# FUZZY_LOGIC_ARDUINO.net
KiCad netlist of a schematic drawn in Altium Designer
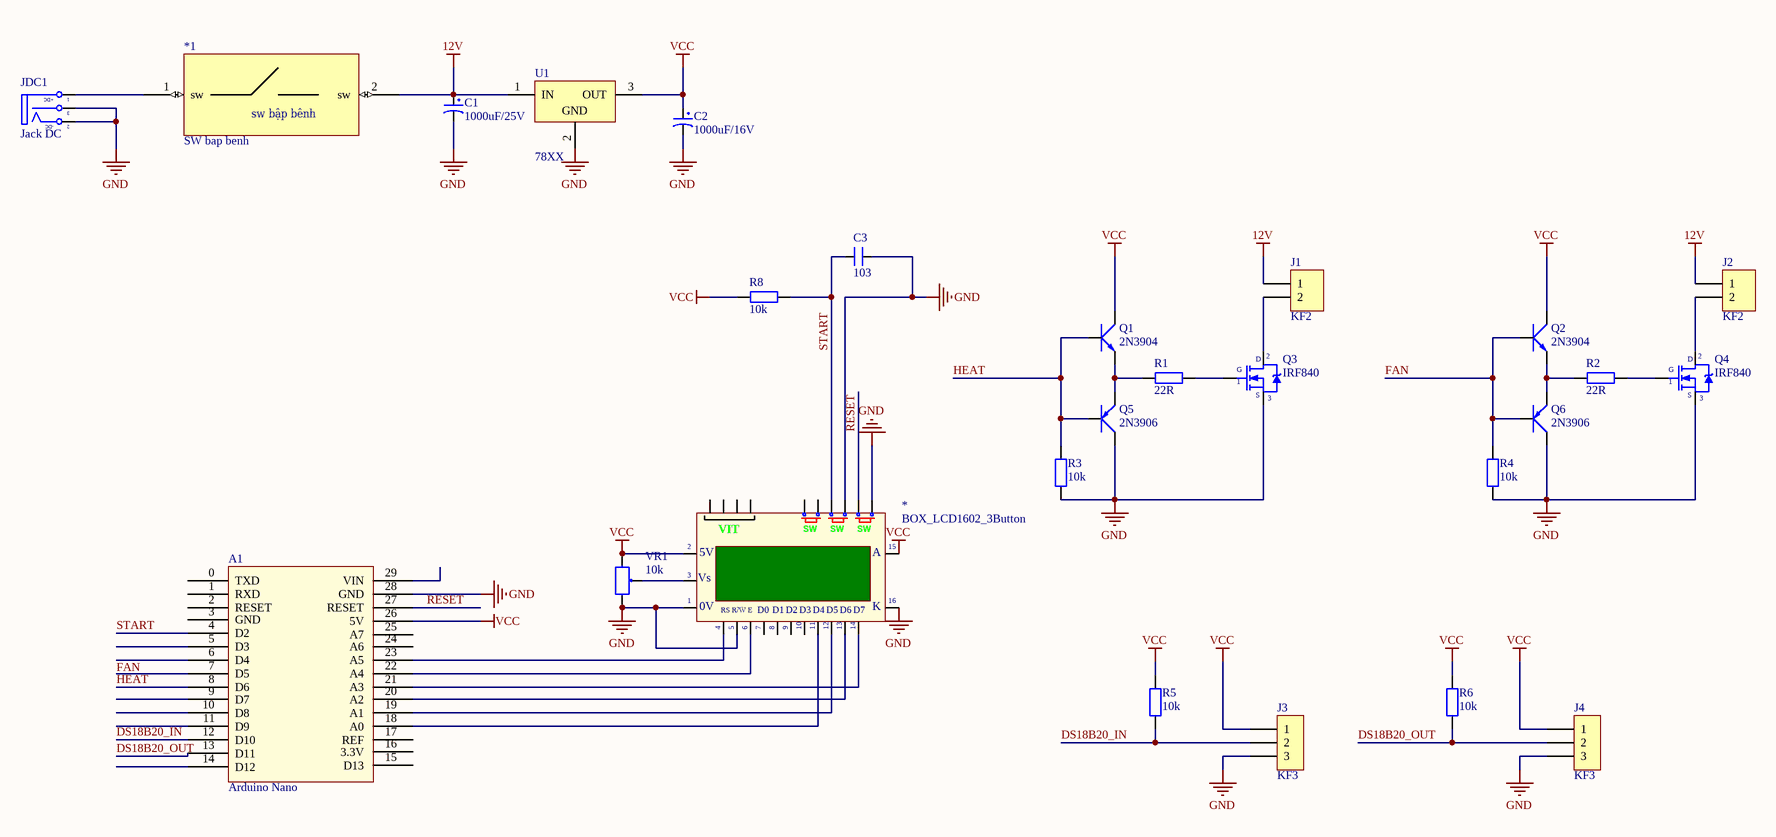
[diagram p0: FUZZY_LOGIC_ARDUINO.SchDoc]

(export (version "E")
  (design (tool "Eeschema 10.0.6"))
  (components
    (comp (ref "*")
      (value "BOX_LCD1602_3Button")
      (footprint "BOX_LCD1602_3Button")
      (libsource (lib "OBIT_TESLA") (part "BOX_LCD1602_3Button"))
    )
    (comp (ref "*1")
      (value "SW bap benh")
      (footprint "SW bapbenh")
      (libsource (lib "Sw bapbenh") (part "SW bap benh"))
    )
    (comp (ref "A1")
      (value "Arduino Nano")
      (footprint "Arduino Nano")
      (libsource (lib "OBIT_TESLA") (part "Arduino Nano"))
    )
    (comp (ref "C1")
      (value "1000uF/25V")
      (footprint "CP1.5/3.4")
      (description "Cap 1000uF/16V - 220uF/50V")
      (libsource (lib "OBIT_TESLA") (part "CP4"))
    )
    (comp (ref "C2")
      (value "1000uF/16V")
      (footprint "CP1.5/3.4")
      (description "Cap 1000uF/16V - 220uF/50V")
      (libsource (lib "OBIT_TESLA") (part "CP4"))
    )
    (comp (ref "C3")
      (value "103")
      (footprint "SM-0805")
      (description "Cap SMD")
      (libsource (lib "OBIT_TESLA") (part "CM"))
    )
    (comp (ref "J1")
      (value "KF2")
      (footprint "KF2-3.5")
      (fields
        (field (name "MANUFACTURER") "Würth Elektronik eiSos GmbH")
        (field (name "PARTNO") "691103110002")
        (field (name "CREATED BY") "Karrer Zheng")
      )
      (libsource (lib "OBIT_TESLA") (part "KF2"))
    )
    (comp (ref "J2")
      (value "KF2")
      (footprint "KF2-3.5")
      (fields
        (field (name "MANUFACTURER") "Würth Elektronik eiSos GmbH")
        (field (name "PARTNO") "691103110002")
        (field (name "CREATED BY") "Karrer Zheng")
      )
      (libsource (lib "OBIT_TESLA") (part "KF2"))
    )
    (comp (ref "J3")
      (value "KF3")
      (footprint "KF3-5.08")
      (fields
        (field (name "MANUFACTURER") "Würth Elektronik eiSos GmbH")
        (field (name "PARTNO") "691103110003")
        (field (name "CREATED BY") "Karrer Zheng")
      )
      (libsource (lib "OBIT_TESLA") (part "KF3"))
    )
    (comp (ref "J4")
      (value "KF3")
      (footprint "KF3-5.08")
      (fields
        (field (name "MANUFACTURER") "Würth Elektronik eiSos GmbH")
        (field (name "PARTNO") "691103110003")
        (field (name "CREATED BY") "Karrer Zheng")
      )
      (libsource (lib "OBIT_TESLA") (part "KF3"))
    )
    (comp (ref "JDC1") (value "Jack DC") (footprint "DC0") (libsource (lib "OBIT_TESLA") (part "JACK_DC")))
    (comp (ref "Q1")
      (value "2N3904")
      (footprint "TO92-123")
      (description "NPN 600mW, ECB")
      (libsource (lib "Tesla_Thinh") (part "2N904"))
    )
    (comp (ref "Q2")
      (value "2N3904")
      (footprint "TO92-123")
      (description "NPN 600mW, ECB")
      (libsource (lib "Tesla_Thinh") (part "2N904"))
    )
    (comp (ref "Q3")
      (value "IRF840")
      (footprint "TO252-123")
      (description "MOSFET N - CHANNEL 500V - 0.75 - 8A - TO-220")
      (libsource (lib "Tesla_Thinh") (part "IRF840"))
    )
    (comp (ref "Q4")
      (value "IRF840")
      (footprint "TO252-123")
      (description "MOSFET N - CHANNEL 500V - 0.75 - 8A - TO-220")
      (libsource (lib "Tesla_Thinh") (part "IRF840"))
    )
    (comp (ref "Q5")
      (value "2N3906")
      (footprint "TO92-123")
      (description "PNP 600mW, ECB")
      (libsource (lib "Tesla_Thinh") (part "2N3906"))
    )
    (comp (ref "Q6")
      (value "2N3906")
      (footprint "TO92-123")
      (description "PNP 600mW, ECB")
      (libsource (lib "Tesla_Thinh") (part "2N3906"))
    )
    (comp (ref "R1")
      (value "22R")
      (footprint "R1/4W")
      (description "Resistor 1/4W")
      (libsource (lib "Tesla_Thinh") (part "R1/4W"))
    )
    (comp (ref "R2")
      (value "22R")
      (footprint "R1/4W")
      (description "Resistor 1/4W")
      (libsource (lib "Tesla_Thinh") (part "R1/4W"))
    )
    (comp (ref "R3")
      (value "10k")
      (footprint "SM-RES-0805")
      (description "Resistor 1/4W")
      (libsource (lib "Tesla_Thinh") (part "R1/4W"))
    )
    (comp (ref "R4")
      (value "10k")
      (footprint "SM-RES-0805")
      (description "Resistor 1/4W")
      (libsource (lib "Tesla_Thinh") (part "R1/4W"))
    )
    (comp (ref "R5")
      (value "10k")
      (footprint "SM-RES-0805")
      (description "Resistor 1/4W")
      (libsource (lib "Tesla_Thinh") (part "R1/4W"))
    )
    (comp (ref "R6")
      (value "10k")
      (footprint "SM-RES-0805")
      (description "Resistor 1/4W")
      (libsource (lib "Tesla_Thinh") (part "R1/4W"))
    )
    (comp (ref "R8")
      (value "10k")
      (footprint "SM-RES-0805")
      (description "Resistor 1/4W")
      (libsource (lib "Tesla_Thinh") (part "R1/4W"))
    )
    (comp (ref "U1") (value "78XX") (footprint "TO252-123") (libsource (lib "OBIT_TESLA") (part "LM78XX")))
    (comp (ref "VR1") (value "10k") (footprint "VR-S2") (libsource (lib "OBIT_TESLA") (part "Resistor Var")))
  )
  (nets
    (net (code "1") (name "/DS18B20_IN") (class "Default")
      (node (ref "A1") (pin "12") (pinfunction "D10_12") (pintype "passive"))
      (node (ref "J3") (pin "2") (pinfunction "2_2") (pintype "passive"))
      (node (ref "R5") (pin "1") (pinfunction "1_1") (pintype "passive"))
    )
    (net (code "2") (name "/DS18B20_OUT") (class "Default")
      (node (ref "A1") (pin "13") (pinfunction "D11_13") (pintype "passive"))
      (node (ref "J4") (pin "2") (pinfunction "2_2") (pintype "passive"))
      (node (ref "R6") (pin "1") (pinfunction "1_1") (pintype "passive"))
    )
    (net (code "3") (name "/FAN") (class "Default")
      (node (ref "Q2") (pin "2") (pinfunction "B_2") (pintype "passive"))
      (node (ref "Q6") (pin "2") (pinfunction "B_2") (pintype "passive"))
      (node (ref "R4") (pin "2") (pinfunction "2_2") (pintype "passive"))
    )
    (net (code "4") (name "/HEAT") (class "Default")
      (node (ref "A1") (pin "8") (pinfunction "D6_8") (pintype "passive"))
      (node (ref "Q1") (pin "2") (pinfunction "B_2") (pintype "passive"))
      (node (ref "Q5") (pin "2") (pinfunction "B_2") (pintype "passive"))
      (node (ref "R3") (pin "2") (pinfunction "2_2") (pintype "passive"))
    )
    (net (code "5") (name "/RESET") (class "Default")
      (node (ref "*") (pin "21") (pinfunction "21_21") (pintype "passive"))
      (node (ref "A1") (pin "27") (pinfunction "RESET_27") (pintype "passive"))
    )
    (net (code "6") (name "/START") (class "Default")
      (node (ref "*") (pin "19") (pinfunction "19_19") (pintype "passive"))
      (node (ref "A1") (pin "4") (pinfunction "D2_4") (pintype "passive"))
      (node (ref "C3") (pin "1") (pinfunction "1_1") (pintype "passive"))
      (node (ref "R8") (pin "1") (pinfunction "1_1") (pintype "passive"))
    )
    (net (code "7") (name "12V") (class "Default")
      (node (ref "*1") (pin "2") (pinfunction "sw_2") (pintype "bidirectional"))
      (node (ref "C1") (pin "1") (pinfunction "1_1") (pintype "passive"))
      (node (ref "J1") (pin "1") (pinfunction "1_1") (pintype "passive"))
      (node (ref "J2") (pin "1") (pinfunction "1_1") (pintype "passive"))
      (node (ref "U1") (pin "1") (pinfunction "IN_1") (pintype "power_in"))
    )
    (net (code "8") (name "GND") (class "Default")
      (node (ref "*") (pin "1") (pinfunction "GND_1") (pintype "passive"))
      (node (ref "*") (pin "16") (pinfunction "K_16") (pintype "passive"))
      (node (ref "*") (pin "20") (pinfunction "20_20") (pintype "passive"))
      (node (ref "*") (pin "22") (pinfunction "22_22") (pintype "passive"))
      (node (ref "*") (pin "5") (pinfunction "R/~{W}_5") (pintype "passive"))
      (node (ref "A1") (pin "28") (pinfunction "GND_28") (pintype "passive"))
      (node (ref "C1") (pin "2") (pinfunction "2_2") (pintype "passive"))
      (node (ref "C2") (pin "2") (pinfunction "2_2") (pintype "passive"))
      (node (ref "C3") (pin "2") (pinfunction "2_2") (pintype "passive"))
      (node (ref "J3") (pin "3") (pinfunction "3_3") (pintype "passive"))
      (node (ref "J4") (pin "3") (pinfunction "3_3") (pintype "passive"))
      (node (ref "JDC1") (pin "2") (pinfunction "TN_2") (pintype "passive"))
      (node (ref "JDC1") (pin "3") (pinfunction "S_3") (pintype "power_in"))
      (node (ref "Q3") (pin "3") (pinfunction "S_3") (pintype "passive"))
      (node (ref "Q4") (pin "3") (pinfunction "S_3") (pintype "passive"))
      (node (ref "Q5") (pin "3") (pinfunction "C_3") (pintype "passive"))
      (node (ref "Q6") (pin "3") (pinfunction "C_3") (pintype "passive"))
      (node (ref "R3") (pin "1") (pinfunction "1_1") (pintype "passive"))
      (node (ref "R4") (pin "1") (pinfunction "1_1") (pintype "passive"))
      (node (ref "U1") (pin "2") (pinfunction "GND_2") (pintype "power_in"))
      (node (ref "VR1") (pin "3") (pinfunction "3_3") (pintype "passive"))
    )
    (net (code "9") (name "Net-(*-D4)") (class "Default")
      (node (ref "*") (pin "11") (pinfunction "D4_11") (pintype "passive"))
      (node (ref "A1") (pin "18") (pinfunction "A0_18") (pintype "passive"))
    )
    (net (code "10") (name "Net-(*-D5)") (class "Default")
      (node (ref "*") (pin "12") (pinfunction "D5_12") (pintype "passive"))
      (node (ref "A1") (pin "19") (pinfunction "A1_19") (pintype "passive"))
    )
    (net (code "11") (name "Net-(*-D6)") (class "Default")
      (node (ref "*") (pin "13") (pinfunction "D6_13") (pintype "passive"))
      (node (ref "A1") (pin "20") (pinfunction "A2_20") (pintype "passive"))
    )
    (net (code "12") (name "Net-(*-D7)") (class "Default")
      (node (ref "*") (pin "14") (pinfunction "D7_14") (pintype "passive"))
      (node (ref "A1") (pin "21") (pinfunction "A3_21") (pintype "passive"))
    )
    (net (code "13") (name "Net-(*-RS)") (class "Default")
      (node (ref "*") (pin "4") (pinfunction "RS_4") (pintype "passive"))
      (node (ref "A1") (pin "23") (pinfunction "A5_23") (pintype "passive"))
    )
    (net (code "14") (name "Net-(*-VEE)") (class "Default")
      (node (ref "*") (pin "3") (pinfunction "VEE_3") (pintype "passive"))
      (node (ref "VR1") (pin "2") (pinfunction "2_2") (pintype "passive"))
    )
    (net (code "15") (name "Net-(*-~{EN})") (class "Default")
      (node (ref "*") (pin "6") (pinfunction "~{EN}_6") (pintype "passive"))
      (node (ref "A1") (pin "22") (pinfunction "A4_22") (pintype "passive"))
    )
    (net (code "16") (name "Net-(JDC1-T)") (class "Default")
      (node (ref "*1") (pin "1") (pinfunction "sw_1") (pintype "bidirectional"))
      (node (ref "JDC1") (pin "1") (pinfunction "T_1") (pintype "passive"))
    )
    (net (code "17") (name "Net-(Q1-E)") (class "Default")
      (node (ref "Q1") (pin "1") (pinfunction "E_1") (pintype "passive"))
      (node (ref "Q5") (pin "1") (pinfunction "E_1") (pintype "passive"))
      (node (ref "R1") (pin "2") (pinfunction "2_2") (pintype "passive"))
    )
    (net (code "18") (name "Net-(Q2-E)") (class "Default")
      (node (ref "Q2") (pin "1") (pinfunction "E_1") (pintype "passive"))
      (node (ref "Q6") (pin "1") (pinfunction "E_1") (pintype "passive"))
      (node (ref "R2") (pin "2") (pinfunction "2_2") (pintype "passive"))
    )
    (net (code "19") (name "Net-(Q3-D)") (class "Default")
      (node (ref "J1") (pin "2") (pinfunction "2_2") (pintype "passive"))
      (node (ref "Q3") (pin "2") (pinfunction "D_2") (pintype "passive"))
    )
    (net (code "20") (name "Net-(Q3-G)") (class "Default")
      (node (ref "Q3") (pin "1") (pinfunction "G_1") (pintype "passive"))
      (node (ref "R1") (pin "1") (pinfunction "1_1") (pintype "passive"))
    )
    (net (code "21") (name "Net-(Q4-D)") (class "Default")
      (node (ref "J2") (pin "2") (pinfunction "2_2") (pintype "passive"))
      (node (ref "Q4") (pin "2") (pinfunction "D_2") (pintype "passive"))
    )
    (net (code "22") (name "Net-(Q4-G)") (class "Default")
      (node (ref "Q4") (pin "1") (pinfunction "G_1") (pintype "passive"))
      (node (ref "R2") (pin "1") (pinfunction "1_1") (pintype "passive"))
    )
    (net (code "23") (name "VCC") (class "Default")
      (node (ref "*") (pin "15") (pinfunction "A_15") (pintype "passive"))
      (node (ref "*") (pin "2") (pinfunction "VDD_2") (pintype "passive"))
      (node (ref "A1") (pin "26") (pinfunction "5V_26") (pintype "passive"))
      (node (ref "C2") (pin "1") (pinfunction "1_1") (pintype "passive"))
      (node (ref "J3") (pin "1") (pinfunction "1_1") (pintype "passive"))
      (node (ref "J4") (pin "1") (pinfunction "1_1") (pintype "passive"))
      (node (ref "Q1") (pin "3") (pinfunction "C_3") (pintype "passive"))
      (node (ref "Q2") (pin "3") (pinfunction "C_3") (pintype "passive"))
      (node (ref "R5") (pin "2") (pinfunction "2_2") (pintype "passive"))
      (node (ref "R6") (pin "2") (pinfunction "2_2") (pintype "passive"))
      (node (ref "R8") (pin "2") (pinfunction "2_2") (pintype "passive"))
      (node (ref "U1") (pin "3") (pinfunction "OUT_3") (pintype "power_in"))
      (node (ref "VR1") (pin "1") (pinfunction "1_1") (pintype "passive"))
    )
    (net (code "24") (name "unconnected-(*-D0-Pad7)") (class "Default")
      (node (ref "*") (pin "7") (pinfunction "D0_7") (pintype "passive"))
    )
    (net (code "25") (name "unconnected-(*-D1-Pad8)") (class "Default")
      (node (ref "*") (pin "8") (pinfunction "D1_8") (pintype "passive"))
    )
    (net (code "26") (name "unconnected-(*-D2-Pad9)") (class "Default")
      (node (ref "*") (pin "9") (pinfunction "D2_9") (pintype "passive"))
    )
    (net (code "27") (name "unconnected-(*-D3-Pad10)") (class "Default")
      (node (ref "*") (pin "10") (pinfunction "D3_10") (pintype "passive"))
    )
    (net (code "28") (name "unconnected-(*-Pad17)") (class "Default")
      (node (ref "*") (pin "17") (pinfunction "17_17") (pintype "passive"))
    )
    (net (code "29") (name "unconnected-(*-Pad18)") (class "Default")
      (node (ref "*") (pin "18") (pinfunction "18_18") (pintype "passive"))
    )
    (net (code "30") (name "unconnected-(*-Pad23)") (class "Default")
      (node (ref "*") (pin "23") (pinfunction "23_23") (pintype "passive"))
    )
    (net (code "31") (name "unconnected-(*-Pad24)") (class "Default")
      (node (ref "*") (pin "24") (pinfunction "24_24") (pintype "passive"))
    )
    (net (code "32") (name "unconnected-(*-Pad25)") (class "Default")
      (node (ref "*") (pin "25") (pinfunction "25_25") (pintype "passive"))
    )
    (net (code "33") (name "unconnected-(*-Pad26)") (class "Default")
      (node (ref "*") (pin "26") (pinfunction "26_26") (pintype "passive"))
    )
    (net (code "34") (name "unconnected-(A1-3.3V-Pad16)") (class "Default")
      (node (ref "A1") (pin "16") (pinfunction "3.3V_16") (pintype "passive"))
    )
    (net (code "35") (name "unconnected-(A1-A6-Pad24)") (class "Default")
      (node (ref "A1") (pin "24") (pinfunction "A6_24") (pintype "passive"))
    )
    (net (code "36") (name "unconnected-(A1-A7-Pad25)") (class "Default")
      (node (ref "A1") (pin "25") (pinfunction "A7_25") (pintype "passive"))
    )
    (net (code "37") (name "unconnected-(A1-D3-Pad5)") (class "Default")
      (node (ref "A1") (pin "5") (pinfunction "D3_5") (pintype "passive"))
    )
    (net (code "38") (name "unconnected-(A1-D4-Pad6)") (class "Default")
      (node (ref "A1") (pin "6") (pinfunction "D4_6") (pintype "passive"))
    )
    (net (code "39") (name "unconnected-(A1-D5-Pad7)") (class "Default")
      (node (ref "A1") (pin "7") (pinfunction "D5_7") (pintype "passive"))
    )
    (net (code "40") (name "unconnected-(A1-D7-Pad9)") (class "Default")
      (node (ref "A1") (pin "9") (pinfunction "D7_9") (pintype "passive"))
    )
    (net (code "41") (name "unconnected-(A1-D8-Pad10)") (class "Default")
      (node (ref "A1") (pin "10") (pinfunction "D8_10") (pintype "passive"))
    )
    (net (code "42") (name "unconnected-(A1-D9-Pad11)") (class "Default")
      (node (ref "A1") (pin "11") (pinfunction "D9_11") (pintype "passive"))
    )
    (net (code "43") (name "unconnected-(A1-D12-Pad14)") (class "Default")
      (node (ref "A1") (pin "14") (pinfunction "D12_14") (pintype "passive"))
    )
    (net (code "44") (name "unconnected-(A1-D13-Pad15)") (class "Default")
      (node (ref "A1") (pin "15") (pinfunction "D13_15") (pintype "passive"))
    )
    (net (code "45") (name "unconnected-(A1-GND-Pad3)") (class "Default")
      (node (ref "A1") (pin "3") (pinfunction "GND_3") (pintype "passive"))
    )
    (net (code "46") (name "unconnected-(A1-REF-Pad17)") (class "Default")
      (node (ref "A1") (pin "17") (pinfunction "REF_17") (pintype "passive"))
    )
    (net (code "47") (name "unconnected-(A1-RESET-Pad2)") (class "Default")
      (node (ref "A1") (pin "2") (pinfunction "RESET_2") (pintype "passive"))
    )
    (net (code "48") (name "unconnected-(A1-RXD-Pad1)") (class "Default")
      (node (ref "A1") (pin "1") (pinfunction "RXD_1") (pintype "passive"))
    )
    (net (code "49") (name "unconnected-(A1-TXD-Pad0)") (class "Default")
      (node (ref "A1") (pin "0") (pinfunction "TXD_0") (pintype "passive"))
    )
    (net (code "50") (name "unconnected-(A1-VIN-Pad29)") (class "Default")
      (node (ref "A1") (pin "29") (pinfunction "VIN_29") (pintype "passive"))
    )
  )
)
